# BW1097_HUB.net
KiCad netlist of a schematic drawn in Altium Designer
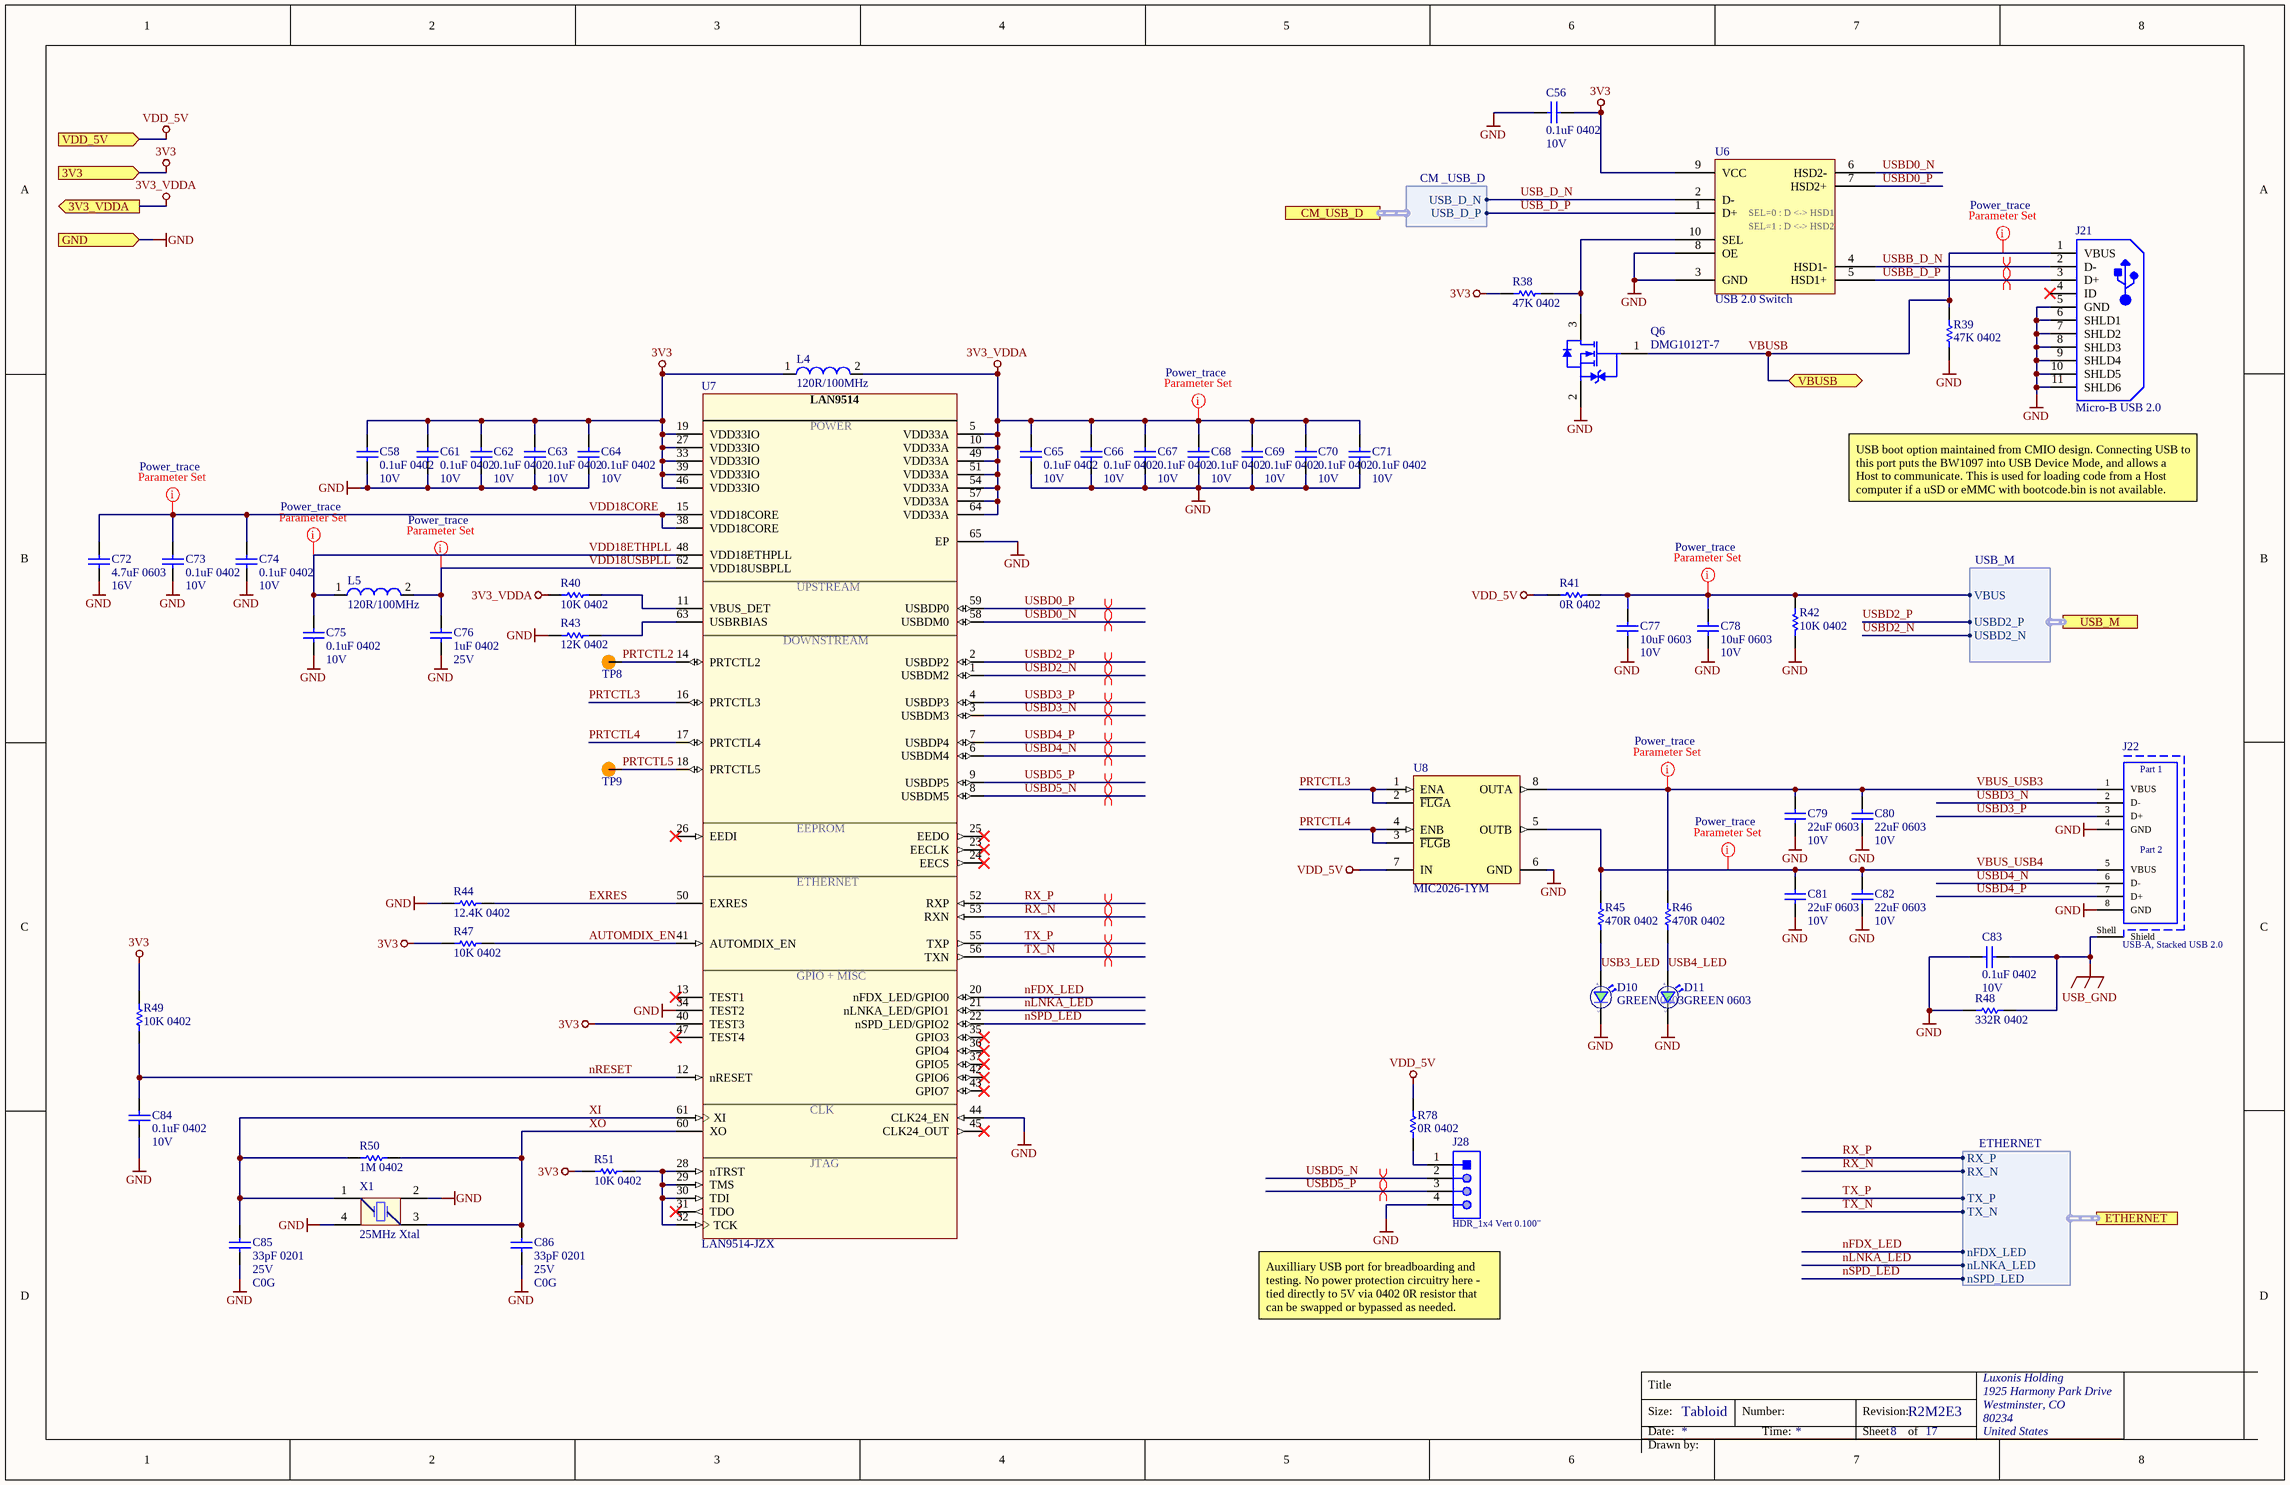
[diagram p0: BW1097_HUB.SchDoc]

(export (version "E")
  (design (tool "Eeschema 10.0.6"))
  (components
    (comp (ref "C56")
      (value "0.1uF 0402")
      (footprint "CAP_Altium_Vault_Generic:CAPC0402(1005)70_N")
      (description "CAP CER 0.1UF 10V X7R 0402 5%")
      (fields (field (name "TOLERANCE") "5%") (field (name "VOLTAGE RATING") "10V"))
      (libsource (lib "LuxonisMaster") (part "GRM155R71A104JA01D"))
    )
    (comp (ref "C58")
      (value "0.1uF 0402")
      (footprint "CAP_Altium_Vault_Generic:CAPC0402(1005)70_N")
      (description "CAP CER 0.1UF 10V X7R 0402 5%")
      (fields (field (name "TOLERANCE") "5%") (field (name "VOLTAGE RATING") "10V"))
      (libsource (lib "LuxonisMaster") (part "GRM155R71A104JA01D"))
    )
    (comp (ref "C61")
      (value "0.1uF 0402")
      (footprint "CAP_Altium_Vault_Generic:CAPC0402(1005)70_N")
      (description "CAP CER 0.1UF 10V X7R 0402 5%")
      (fields (field (name "TOLERANCE") "5%") (field (name "VOLTAGE RATING") "10V"))
      (libsource (lib "LuxonisMaster") (part "GRM155R71A104JA01D"))
    )
    (comp (ref "C62")
      (value "0.1uF 0402")
      (footprint "CAP_Altium_Vault_Generic:CAPC0402(1005)70_N")
      (description "CAP CER 0.1UF 10V X7R 0402 5%")
      (fields (field (name "TOLERANCE") "5%") (field (name "VOLTAGE RATING") "10V"))
      (libsource (lib "LuxonisMaster") (part "GRM155R71A104JA01D"))
    )
    (comp (ref "C63")
      (value "0.1uF 0402")
      (footprint "CAP_Altium_Vault_Generic:CAPC0402(1005)70_N")
      (description "CAP CER 0.1UF 10V X7R 0402 5%")
      (fields (field (name "TOLERANCE") "5%") (field (name "VOLTAGE RATING") "10V"))
      (libsource (lib "LuxonisMaster") (part "GRM155R71A104JA01D"))
    )
    (comp (ref "C64")
      (value "0.1uF 0402")
      (footprint "CAP_Altium_Vault_Generic:CAPC0402(1005)70_N")
      (description "CAP CER 0.1UF 10V X7R 0402 5%")
      (fields (field (name "TOLERANCE") "5%") (field (name "VOLTAGE RATING") "10V"))
      (libsource (lib "LuxonisMaster") (part "GRM155R71A104JA01D"))
    )
    (comp (ref "C65")
      (value "0.1uF 0402")
      (footprint "CAP_Altium_Vault_Generic:CAPC0402(1005)70_N")
      (description "CAP CER 0.1UF 10V X7R 0402 5%")
      (fields (field (name "TOLERANCE") "5%") (field (name "VOLTAGE RATING") "10V"))
      (libsource (lib "LuxonisMaster") (part "GRM155R71A104JA01D"))
    )
    (comp (ref "C66")
      (value "0.1uF 0402")
      (footprint "CAP_Altium_Vault_Generic:CAPC0402(1005)70_N")
      (description "CAP CER 0.1UF 10V X7R 0402 5%")
      (fields (field (name "TOLERANCE") "5%") (field (name "VOLTAGE RATING") "10V"))
      (libsource (lib "LuxonisMaster") (part "GRM155R71A104JA01D"))
    )
    (comp (ref "C67")
      (value "0.1uF 0402")
      (footprint "CAP_Altium_Vault_Generic:CAPC0402(1005)70_N")
      (description "CAP CER 0.1UF 10V X7R 0402 5%")
      (fields (field (name "TOLERANCE") "5%") (field (name "VOLTAGE RATING") "10V"))
      (libsource (lib "LuxonisMaster") (part "GRM155R71A104JA01D"))
    )
    (comp (ref "C68")
      (value "0.1uF 0402")
      (footprint "CAP_Altium_Vault_Generic:CAPC0402(1005)70_N")
      (description "CAP CER 0.1UF 10V X7R 0402 5%")
      (fields (field (name "TOLERANCE") "5%") (field (name "VOLTAGE RATING") "10V"))
      (libsource (lib "LuxonisMaster") (part "GRM155R71A104JA01D"))
    )
    (comp (ref "C69")
      (value "0.1uF 0402")
      (footprint "CAP_Altium_Vault_Generic:CAPC0402(1005)70_N")
      (description "CAP CER 0.1UF 10V X7R 0402 5%")
      (fields (field (name "TOLERANCE") "5%") (field (name "VOLTAGE RATING") "10V"))
      (libsource (lib "LuxonisMaster") (part "GRM155R71A104JA01D"))
    )
    (comp (ref "C70")
      (value "0.1uF 0402")
      (footprint "CAP_Altium_Vault_Generic:CAPC0402(1005)70_N")
      (description "CAP CER 0.1UF 10V X7R 0402 5%")
      (fields (field (name "TOLERANCE") "5%") (field (name "VOLTAGE RATING") "10V"))
      (libsource (lib "LuxonisMaster") (part "GRM155R71A104JA01D"))
    )
    (comp (ref "C71")
      (value "0.1uF 0402")
      (footprint "CAP_Altium_Vault_Generic:CAPC0402(1005)70_N")
      (description "CAP CER 0.1UF 10V X7R 0402 5%")
      (fields (field (name "TOLERANCE") "5%") (field (name "VOLTAGE RATING") "10V"))
      (libsource (lib "LuxonisMaster") (part "GRM155R71A104JA01D"))
    )
    (comp (ref "C72")
      (value "4.7uF 0603")
      (footprint "CAP_Altium_Vault_Generic:CAPC0603(1608)100_N")
      (description "CAP CER 4.7UF 16V X5R 0603 10%")
      (fields (field (name "TOLERANCE") "10%") (field (name "VOLTAGE RATING") "16V"))
      (libsource (lib "LuxonisMaster") (part "GRM188R61C475KAAJD"))
    )
    (comp (ref "C73")
      (value "0.1uF 0402")
      (footprint "CAP_Altium_Vault_Generic:CAPC0402(1005)70_N")
      (description "CAP CER 0.1UF 10V X7R 0402 5%")
      (fields (field (name "TOLERANCE") "5%") (field (name "VOLTAGE RATING") "10V"))
      (libsource (lib "LuxonisMaster") (part "GRM155R71A104JA01D"))
    )
    (comp (ref "C74")
      (value "0.1uF 0402")
      (footprint "CAP_Altium_Vault_Generic:CAPC0402(1005)70_N")
      (description "CAP CER 0.1UF 10V X7R 0402 5%")
      (fields (field (name "TOLERANCE") "5%") (field (name "VOLTAGE RATING") "10V"))
      (libsource (lib "LuxonisMaster") (part "GRM155R71A104JA01D"))
    )
    (comp (ref "C75")
      (value "0.1uF 0402")
      (footprint "CAP_Altium_Vault_Generic:CAPC0402(1005)70_N")
      (description "CAP CER 0.1UF 10V X7R 0402 5%")
      (fields (field (name "TOLERANCE") "5%") (field (name "VOLTAGE RATING") "10V"))
      (libsource (lib "LuxonisMaster") (part "GRM155R71A104JA01D"))
    )
    (comp (ref "C76")
      (value "1uF 0402")
      (footprint "CAP_Altium_Vault_Generic:CAPC0402(1005)70_N")
      (description "CAP CER 1UF 25V X5R 0402 10%")
      (fields
        (field (name "TOLERANCE") "10%")
        (field (name "VOLTAGE") "25V")
        (field (name "VOLTAGE RATING") "25V")
      )
      (libsource (lib "LuxonisMaster") (part "GRM155R61E105KA12D"))
    )
    (comp (ref "C77")
      (value "10uF 0603")
      (footprint "CAP_Altium_Vault_Generic:CAPC0603(1608)100_N")
      (description "CAP CER 10UF 10V X5R 0603 20%")
      (fields (field (name "TOLERANCE") "20%") (field (name "VOLTAGE RATING") "10V"))
      (libsource (lib "LuxonisMaster") (part "GRM188R61A106ME69D"))
    )
    (comp (ref "C78")
      (value "10uF 0603")
      (footprint "CAP_Altium_Vault_Generic:CAPC0603(1608)100_N")
      (description "CAP CER 10UF 10V X5R 0603 20%")
      (fields (field (name "TOLERANCE") "20%") (field (name "VOLTAGE RATING") "10V"))
      (libsource (lib "LuxonisMaster") (part "GRM188R61A106ME69D"))
    )
    (comp (ref "C79")
      (value "22uF 0603")
      (footprint "CAP_Altium_Vault_Generic:CAPC0603(1608)100_N")
      (description "CAP CER 22UF 10V X5R 0603 20%")
      (fields (field (name "TOLERANCE") "20%") (field (name "VOLTAGE RATING") "10V"))
      (libsource (lib "LuxonisMaster") (part "GRM188R61A226ME15D"))
    )
    (comp (ref "C80")
      (value "22uF 0603")
      (footprint "CAP_Altium_Vault_Generic:CAPC0603(1608)100_N")
      (description "CAP CER 22UF 10V X5R 0603 20%")
      (fields (field (name "TOLERANCE") "20%") (field (name "VOLTAGE RATING") "10V"))
      (libsource (lib "LuxonisMaster") (part "GRM188R61A226ME15D"))
    )
    (comp (ref "C81")
      (value "22uF 0603")
      (footprint "CAP_Altium_Vault_Generic:CAPC0603(1608)100_N")
      (description "CAP CER 22UF 10V X5R 0603 20%")
      (fields (field (name "TOLERANCE") "20%") (field (name "VOLTAGE RATING") "10V"))
      (libsource (lib "LuxonisMaster") (part "GRM188R61A226ME15D"))
    )
    (comp (ref "C82")
      (value "22uF 0603")
      (footprint "CAP_Altium_Vault_Generic:CAPC0603(1608)100_N")
      (description "CAP CER 22UF 10V X5R 0603 20%")
      (fields (field (name "TOLERANCE") "20%") (field (name "VOLTAGE RATING") "10V"))
      (libsource (lib "LuxonisMaster") (part "GRM188R61A226ME15D"))
    )
    (comp (ref "C83")
      (value "0.1uF 0402")
      (footprint "CAP_Altium_Vault_Generic:CAPC0402(1005)70_N")
      (description "CAP CER 0.1UF 10V X7R 0402 5%")
      (fields (field (name "TOLERANCE") "5%") (field (name "VOLTAGE RATING") "10V"))
      (libsource (lib "LuxonisMaster") (part "GRM155R71A104JA01D"))
    )
    (comp (ref "C84")
      (value "0.1uF 0402")
      (footprint "CAP_Altium_Vault_Generic:CAPC0402(1005)70_N")
      (description "CAP CER 0.1UF 10V X7R 0402 5%")
      (fields (field (name "TOLERANCE") "5%") (field (name "VOLTAGE RATING") "10V"))
      (libsource (lib "LuxonisMaster") (part "GRM155R71A104JA01D"))
    )
    (comp (ref "C85")
      (value "33pF 0201")
      (footprint "CAP_Altium_Vault_Generic:CAPC0201(0603)33_L")
      (description "CAP CER 33PF 25V C0G/NP0 0201")
      (fields
        (field (name "TOLERANCE") "5%")
        (field (name "VOLTAGE RATING") "25V")
        (field (name "DIELECTRIC") "C0G")
      )
      (libsource (lib "LuxonisMaster") (part "GRM0335C1E330JA01D"))
    )
    (comp (ref "C86")
      (value "33pF 0201")
      (footprint "CAP_Altium_Vault_Generic:CAPC0201(0603)33_L")
      (description "CAP CER 33PF 25V C0G/NP0 0201")
      (fields
        (field (name "TOLERANCE") "5%")
        (field (name "VOLTAGE RATING") "25V")
        (field (name "DIELECTRIC") "C0G")
      )
      (libsource (lib "LuxonisMaster") (part "GRM0335C1E330JA01D"))
    )
    (comp (ref "D10")
      (value "GREEN 0603")
      (footprint "LuxonisMaster:SML_D1xx8W")
      (description "LED GREEN DIFFUSED 0603 SMD Green 572nm LED Indication - Discrete 2.2V 0603 (1608 Metric)")
      (fields (field (name "MANUFACTURER") "Rohm") (field (name "MANUFACTURER PART NUMBER") "SML-D12M8WT86"))
      (libsource (lib "LuxonisMaster") (part "SML-D12M8WT86"))
    )
    (comp (ref "D11")
      (value "GREEN 0603")
      (footprint "LuxonisMaster:SML_D1xx8W")
      (description "LED GREEN DIFFUSED 0603 SMD Green 572nm LED Indication - Discrete 2.2V 0603 (1608 Metric)")
      (fields (field (name "MANUFACTURER") "Rohm") (field (name "MANUFACTURER PART NUMBER") "SML-D12M8WT86"))
      (libsource (lib "LuxonisMaster") (part "SML-D12M8WT86"))
    )
    (comp (ref "J21")
      (value "Micro-B USB 2.0")
      (footprint "LuxonisMaster:10118194-0001LF")
      (libsource (lib "LuxonisMaster") (part "10118194-0001LF"))
    )
    (comp (ref "J22")
      (value "USB-A, Stacked USB 2.0")
      (footprint "LuxonisMaster:61400826021")
      (libsource (lib "LuxonisMaster") (part "61400826021"))
    )
    (comp (ref "J28")
      (value "HDR_1x4 Vert 0.100\"")
      (footprint "LuxonisMaster:61300411121")
      (description "CONN HEADER VERT 4POS 2.54MM  Connector Header Through Hole 4 position 0.100\" (2.54mm)")
      (libsource (lib "LuxonisMaster") (part "61300411121"))
    )
    (comp (ref "L4")
      (value "120R/100MHz")
      (footprint "LuxonisMaster:BLM18PG121SN1D_N")
      (description "FERRITE BEAD 120 OHM 0603 1LN")
      (fields (field (name "TOLERANCE") "25%"))
      (libsource (lib "LuxonisMaster") (part "BLM18PG121SN1D"))
    )
    (comp (ref "L5")
      (value "120R/100MHz")
      (footprint "LuxonisMaster:BLM18PG121SN1D_N")
      (description "FERRITE BEAD 120 OHM 0603 1LN")
      (fields (field (name "TOLERANCE") "25%"))
      (libsource (lib "LuxonisMaster") (part "BLM18PG121SN1D"))
    )
    (comp (ref "Q6")
      (value "DMG1012T-7")
      (footprint "LuxonisMaster:DMG1012T-7")
      (description "MOSFET N-CH 20V 630MA SOT-523")
      (libsource (lib "LuxonisMaster") (part "DMG1012T-7"))
    )
    (comp (ref "R38")
      (value "47K 0402")
      (footprint "RES_Altium_Vault_Generic:RESC0402(1005)_N")
      (description "RES SMD 47K OHM 1% 1/16W 0402")
      (fields (field (name "TOLERANCE") "1%"))
      (libsource (lib "LuxonisMaster") (part "RC0402FR-0747KL"))
    )
    (comp (ref "R39")
      (value "47K 0402")
      (footprint "RES_Altium_Vault_Generic:RESC0402(1005)_N")
      (description "RES SMD 47K OHM 1% 1/16W 0402")
      (fields (field (name "TOLERANCE") "1%"))
      (libsource (lib "LuxonisMaster") (part "RC0402FR-0747KL"))
    )
    (comp (ref "R40")
      (value "10K 0402")
      (footprint "RES_Altium_Vault_Generic:RESC0402(1005)_N")
      (fields (field (name "TOLERANCE") "1%"))
      (libsource (lib "LuxonisMaster") (part "RC0402FR-1310KL"))
    )
    (comp (ref "R41")
      (value "0R 0402")
      (footprint "RES_Altium_Vault_Generic:RESC0402(1005)_N")
      (description "RES SMD 0 OHM JUMPER 1/16W 0402")
      (fields (field (name "TOLERANCE") "5%"))
      (libsource (lib "LuxonisMaster") (part "CRCW04020000Z0ED"))
    )
    (comp (ref "R42")
      (value "10K 0402")
      (footprint "RES_Altium_Vault_Generic:RESC0402(1005)_N")
      (fields (field (name "TOLERANCE") "1%"))
      (libsource (lib "LuxonisMaster") (part "RC0402FR-1310KL"))
    )
    (comp (ref "R43")
      (value "12K 0402")
      (footprint "RES_Altium_Vault_Generic:RESC0402(1005)_N")
      (fields (field (name "TOLERANCE") "1%"))
      (libsource (lib "LuxonisMaster") (part "RC0402FR-0712KL"))
    )
    (comp (ref "R44")
      (value "12.4K 0402")
      (footprint "RES_Altium_Vault_Generic:RESC0402(1005)_N")
      (description "RES SMD 12.4K OHM 1% 1/16W 0402")
      (fields (field (name "TOLERANCE") "1%"))
      (libsource (lib "LuxonisMaster") (part "RC0402FR-0712K4L"))
    )
    (comp (ref "R45")
      (value "470R 0402")
      (footprint "RES_Altium_Vault_Generic:RESC0402(1005)_N")
      (description "RES SMD 470 OHM 1% 1/16W 0402")
      (fields (field (name "TOLERANCE") "1%"))
      (libsource (lib "LuxonisMaster") (part "CRCW0402470RFKED"))
    )
    (comp (ref "R46")
      (value "470R 0402")
      (footprint "RES_Altium_Vault_Generic:RESC0402(1005)_N")
      (description "RES SMD 470 OHM 1% 1/16W 0402")
      (fields (field (name "TOLERANCE") "1%"))
      (libsource (lib "LuxonisMaster") (part "CRCW0402470RFKED"))
    )
    (comp (ref "R47")
      (value "10K 0402")
      (footprint "RES_Altium_Vault_Generic:RESC0402(1005)_N")
      (fields (field (name "TOLERANCE") "1%"))
      (libsource (lib "LuxonisMaster") (part "RC0402FR-1310KL"))
    )
    (comp (ref "R48")
      (value "332R 0402")
      (footprint "RES_Altium_Vault_Generic:RESC0402(1005)_N")
      (description "RES SMD 332 OHM 1% 1/16W 0402")
      (fields (field (name "TOLERANCE") "1%"))
      (libsource (lib "LuxonisMaster") (part "RC0402FR-07332RL"))
    )
    (comp (ref "R49")
      (value "10K 0402")
      (footprint "RES_Altium_Vault_Generic:RESC0402(1005)_N")
      (fields (field (name "TOLERANCE") "1%"))
      (libsource (lib "LuxonisMaster") (part "RC0402FR-1310KL"))
    )
    (comp (ref "R50")
      (value "1M 0402")
      (footprint "RES_Altium_Vault_Generic:RESC0402(1005)_N")
      (description "RES SMD 1M OHM 1% 1/16W 0402")
      (fields (field (name "TOLERANCE") "1%"))
      (libsource (lib "LuxonisMaster") (part "RC0402FR-071ML"))
    )
    (comp (ref "R51")
      (value "10K 0402")
      (footprint "RES_Altium_Vault_Generic:RESC0402(1005)_N")
      (fields (field (name "TOLERANCE") "1%"))
      (libsource (lib "LuxonisMaster") (part "RC0402FR-1310KL"))
    )
    (comp (ref "R78")
      (value "0R 0402")
      (footprint "RES_Altium_Vault_Generic:RESC0402(1005)_N")
      (description "RES SMD 0 OHM JUMPER 1/16W 0402")
      (fields (field (name "TOLERANCE") "5%"))
      (libsource (lib "LuxonisMaster") (part "CRCW04020000Z0ED"))
    )
    (comp (ref "TP8")
      (value "TP100_200_NS")
      (footprint "LuxonisMaster:TP100_200_NS")
      (libsource (lib "LuxonisMaster") (part "TEST_POINT"))
    )
    (comp (ref "TP9")
      (value "TP100_200_NS")
      (footprint "LuxonisMaster:TP100_200_NS")
      (libsource (lib "LuxonisMaster") (part "TEST_POINT"))
    )
    (comp (ref "U6")
      (value "USB 2.0 Switch")
      (footprint "LuxonisMaster:FSUSB42UMX")
      (description "IC USB SWITCH DPDT 10UMLP")
      (libsource (lib "LuxonisMaster") (part "FSUSB42UMX"))
    )
    (comp (ref "U7")
      (value "LAN9514-JZX")
      (footprint "LuxonisMaster:LAN951x-JZX")
      (libsource (lib "LuxonisMaster") (part "LAN9514-JZX"))
    )
    (comp (ref "U8")
      (value "MIC2026-1YM")
      (footprint "LuxonisMaster:MIC2026-1YM")
      (description "IC PW DIST SW DUAL 8SOIC Power Switch/Driver 1:2 N-Channel 500mA 8-SOIC")
      (fields (field (name "MANUFACTURER") "Micrel"))
      (libsource (lib "LuxonisMaster") (part "MIC2026-1YM"))
    )
    (comp (ref "X1")
      (value "25MHz Xtal")
      (footprint "LuxonisMaster:8Z-25.000MAAJ-T")
      (description "CRYSTAL 25.0000MHZ 18PF SMD")
      (fields (field (name "TOLERANCE") "30ppm"))
      (libsource (lib "LuxonisMaster") (part "8Z-25.000MAAJ-T"))
    )
  )
  (nets
    (net (code "5") (name "/AUTOMDIX_EN") (class "Default")
      (node (ref "R47") (pin "2") (pinfunction "2_2") (pintype "passive"))
      (node (ref "U7") (pin "41") (pinfunction "AUTOMDIX_EN_41") (pintype "input"))
    )
    (net (code "6") (name "/EXRES") (class "Default")
      (node (ref "R44") (pin "2") (pinfunction "2_2") (pintype "passive"))
      (node (ref "U7") (pin "50") (pinfunction "EXRES_50") (pintype "passive"))
    )
    (net (code "7") (name "/PRTCTL2") (class "Default")
      (node (ref "TP8") (pin "1") (pintype "passive"))
      (node (ref "U7") (pin "14") (pinfunction "PRTCTL2_14") (pintype "bidirectional"))
    )
    (net (code "8") (name "/PRTCTL3") (class "Default")
      (node (ref "U7") (pin "16") (pinfunction "PRTCTL3_16") (pintype "bidirectional"))
      (node (ref "U8") (pin "1") (pinfunction "ENA_1") (pintype "input"))
      (node (ref "U8") (pin "2") (pinfunction "~{FLG}A_2") (pintype "open_collector"))
    )
    (net (code "9") (name "/PRTCTL4") (class "Default")
      (node (ref "U7") (pin "17") (pinfunction "PRTCTL4_17") (pintype "bidirectional"))
      (node (ref "U8") (pin "3") (pinfunction "~{FLG}B_3") (pintype "open_collector"))
      (node (ref "U8") (pin "4") (pinfunction "ENB_4") (pintype "input"))
    )
    (net (code "10") (name "/PRTCTL5") (class "Default")
      (node (ref "TP9") (pin "1") (pintype "passive"))
      (node (ref "U7") (pin "18") (pinfunction "PRTCTL5_18") (pintype "bidirectional"))
    )
    (net (code "11") (name "/RX_N") (class "Default")
      (node (ref "U7") (pin "53") (pinfunction "RXN_53") (pintype "input"))
    )
    (net (code "12") (name "/RX_P") (class "Default")
      (node (ref "U7") (pin "52") (pinfunction "RXP_52") (pintype "input"))
    )
    (net (code "13") (name "/TX_N") (class "Default")
      (node (ref "U7") (pin "56") (pinfunction "TXN_56") (pintype "output"))
    )
    (net (code "14") (name "/TX_P") (class "Default")
      (node (ref "U7") (pin "55") (pinfunction "TXP_55") (pintype "output"))
    )
    (net (code "15") (name "/USB3_LED") (class "Default")
      (node (ref "D10") (pin "2") (pinfunction "A_2") (pintype "passive"))
      (node (ref "R45") (pin "1") (pinfunction "1_1") (pintype "passive"))
    )
    (net (code "16") (name "/USB4_LED") (class "Default")
      (node (ref "D11") (pin "2") (pinfunction "A_2") (pintype "passive"))
      (node (ref "R46") (pin "1") (pinfunction "1_1") (pintype "passive"))
    )
    (net (code "17") (name "/USBB_D_N") (class "Default")
      (node (ref "J21") (pin "2") (pinfunction "D-_2") (pintype "passive"))
      (node (ref "U6") (pin "4") (pinfunction "HSD1-_4") (pintype "passive"))
    )
    (net (code "18") (name "/USBB_D_P") (class "Default")
      (node (ref "J21") (pin "3") (pinfunction "D+_3") (pintype "passive"))
      (node (ref "U6") (pin "5") (pinfunction "HSD1+_5") (pintype "passive"))
    )
    (net (code "19") (name "/USBD0_N") (class "Default")
      (node (ref "U6") (pin "6") (pinfunction "HSD2-_6") (pintype "passive"))
      (node (ref "U7") (pin "58") (pinfunction "USBDM0_58") (pintype "bidirectional"))
    )
    (net (code "20") (name "/USBD0_P") (class "Default")
      (node (ref "U6") (pin "7") (pinfunction "HSD2+_7") (pintype "passive"))
      (node (ref "U7") (pin "59") (pinfunction "USBDP0_59") (pintype "bidirectional"))
    )
    (net (code "21") (name "/USBD2_N") (class "Default")
      (node (ref "U7") (pin "1") (pinfunction "USBDM2_1") (pintype "bidirectional"))
    )
    (net (code "22") (name "/USBD2_P") (class "Default")
      (node (ref "U7") (pin "2") (pinfunction "USBDP2_2") (pintype "bidirectional"))
    )
    (net (code "23") (name "/USBD3_N") (class "Default")
      (node (ref "J22") (pin "2") (pinfunction "D-_2") (pintype "passive"))
      (node (ref "U7") (pin "3") (pinfunction "USBDM3_3") (pintype "bidirectional"))
    )
    (net (code "24") (name "/USBD3_P") (class "Default")
      (node (ref "J22") (pin "3") (pinfunction "D+_3") (pintype "passive"))
      (node (ref "U7") (pin "4") (pinfunction "USBDP3_4") (pintype "bidirectional"))
    )
    (net (code "25") (name "/USBD4_N") (class "Default")
      (node (ref "J22") (pin "6") (pinfunction "D-_6") (pintype "passive"))
      (node (ref "U7") (pin "6") (pinfunction "USBDM4_6") (pintype "bidirectional"))
    )
    (net (code "26") (name "/USBD4_P") (class "Default")
      (node (ref "J22") (pin "7") (pinfunction "D+_7") (pintype "passive"))
      (node (ref "U7") (pin "7") (pinfunction "USBDP4_7") (pintype "bidirectional"))
    )
    (net (code "27") (name "/USBD5_N") (class "Default")
      (node (ref "J28") (pin "2") (pinfunction "2_2") (pintype "passive"))
      (node (ref "U7") (pin "8") (pinfunction "USBDM5_8") (pintype "bidirectional"))
    )
    (net (code "28") (name "/USBD5_P") (class "Default")
      (node (ref "J28") (pin "3") (pinfunction "3_3") (pintype "passive"))
      (node (ref "U7") (pin "9") (pinfunction "USBDP5_9") (pintype "bidirectional"))
    )
    (net (code "29") (name "/USB_D_N") (class "Default")
      (node (ref "U6") (pin "2") (pinfunction "D-_2") (pintype "passive"))
    )
    (net (code "30") (name "/USB_D_P") (class "Default")
      (node (ref "U6") (pin "1") (pinfunction "D+_1") (pintype "passive"))
    )
    (net (code "31") (name "/VBUSB") (class "Default")
      (node (ref "J21") (pin "1") (pinfunction "VBUS_1") (pintype "passive"))
      (node (ref "Q6") (pin "1") (pinfunction "1_1") (pintype "passive"))
      (node (ref "R39") (pin "2") (pinfunction "2_2") (pintype "passive"))
    )
    (net (code "32") (name "/VBUS_USB3") (class "Default")
      (node (ref "C79") (pin "1") (pinfunction "1_1") (pintype "passive"))
      (node (ref "C80") (pin "1") (pinfunction "1_1") (pintype "passive"))
      (node (ref "J22") (pin "1") (pinfunction "VBUS_1") (pintype "passive"))
      (node (ref "R46") (pin "2") (pinfunction "2_2") (pintype "passive"))
      (node (ref "U8") (pin "8") (pinfunction "OUTA_8") (pintype "output"))
    )
    (net (code "33") (name "/VBUS_USB4") (class "Default")
      (node (ref "C81") (pin "1") (pinfunction "1_1") (pintype "passive"))
      (node (ref "C82") (pin "1") (pinfunction "1_1") (pintype "passive"))
      (node (ref "J22") (pin "5") (pinfunction "VBUS_5") (pintype "passive"))
      (node (ref "R45") (pin "2") (pinfunction "2_2") (pintype "passive"))
      (node (ref "U8") (pin "5") (pinfunction "OUTB_5") (pintype "output"))
    )
    (net (code "34") (name "/VDD18CORE") (class "Default")
      (node (ref "C72") (pin "2") (pinfunction "2_2") (pintype "passive"))
      (node (ref "C73") (pin "2") (pinfunction "2_2") (pintype "passive"))
      (node (ref "C74") (pin "2") (pinfunction "2_2") (pintype "passive"))
      (node (ref "U7") (pin "15") (pinfunction "VDD18CORE_15") (pintype "power_in"))
      (node (ref "U7") (pin "38") (pinfunction "VDD18CORE_38") (pintype "power_in"))
    )
    (net (code "35") (name "/VDD18ETHPLL") (class "Default")
      (node (ref "C75") (pin "2") (pinfunction "2_2") (pintype "passive"))
      (node (ref "L5") (pin "1") (pinfunction "1_1") (pintype "passive"))
      (node (ref "U7") (pin "48") (pinfunction "VDD18ETHPLL_48") (pintype "power_in"))
    )
    (net (code "36") (name "/VDD18USBPLL") (class "Default")
      (node (ref "C76") (pin "2") (pinfunction "2_2") (pintype "passive"))
      (node (ref "L5") (pin "2") (pinfunction "2_2") (pintype "passive"))
      (node (ref "U7") (pin "62") (pinfunction "VDD18USBPLL_62") (pintype "power_in"))
    )
    (net (code "37") (name "/XI") (class "Default")
      (node (ref "C85") (pin "2") (pinfunction "2_2") (pintype "passive"))
      (node (ref "R50") (pin "1") (pinfunction "1_1") (pintype "passive"))
      (node (ref "U7") (pin "61") (pinfunction "XI_61") (pintype "input"))
      (node (ref "X1") (pin "1") (pinfunction "OSC1_1") (pintype "passive"))
    )
    (net (code "38") (name "/XO") (class "Default")
      (node (ref "C86") (pin "2") (pinfunction "2_2") (pintype "passive"))
      (node (ref "R50") (pin "2") (pinfunction "2_2") (pintype "passive"))
      (node (ref "U7") (pin "60") (pinfunction "XO_60") (pintype "passive"))
      (node (ref "X1") (pin "3") (pinfunction "OSC3_3") (pintype "passive"))
    )
    (net (code "39") (name "/nFDX_LED") (class "Default")
      (node (ref "U7") (pin "20") (pinfunction "nFDX_LED/GPIO0_20") (pintype "bidirectional"))
    )
    (net (code "40") (name "/nLNKA_LED") (class "Default")
      (node (ref "U7") (pin "21") (pinfunction "nLNKA_LED/GPIO1_21") (pintype "bidirectional"))
    )
    (net (code "41") (name "/nRESET") (class "Default")
      (node (ref "C84") (pin "2") (pinfunction "2_2") (pintype "passive"))
      (node (ref "R49") (pin "2") (pinfunction "2_2") (pintype "passive"))
      (node (ref "U7") (pin "12") (pinfunction "nRESET_12") (pintype "input"))
    )
    (net (code "42") (name "/nSPD_LED") (class "Default")
      (node (ref "U7") (pin "22") (pinfunction "nSPD_LED/GPIO2_22") (pintype "bidirectional"))
    )
    (net (code "46") (name "3V3") (class "Default")
      (node (ref "C56") (pin "1") (pinfunction "1_1") (pintype "passive"))
      (node (ref "C58") (pin "2") (pinfunction "2_2") (pintype "passive"))
      (node (ref "C61") (pin "2") (pinfunction "2_2") (pintype "passive"))
      (node (ref "C62") (pin "2") (pinfunction "2_2") (pintype "passive"))
      (node (ref "C63") (pin "2") (pinfunction "2_2") (pintype "passive"))
      (node (ref "C64") (pin "2") (pinfunction "2_2") (pintype "passive"))
      (node (ref "L4") (pin "1") (pinfunction "1_1") (pintype "passive"))
      (node (ref "R38") (pin "1") (pinfunction "1_1") (pintype "passive"))
      (node (ref "R47") (pin "1") (pinfunction "1_1") (pintype "passive"))
      (node (ref "R49") (pin "1") (pinfunction "1_1") (pintype "passive"))
      (node (ref "R51") (pin "1") (pinfunction "1_1") (pintype "passive"))
      (node (ref "U6") (pin "9") (pinfunction "VCC_9") (pintype "passive"))
      (node (ref "U7") (pin "19") (pinfunction "VDD33IO_19") (pintype "power_in"))
      (node (ref "U7") (pin "27") (pinfunction "VDD33IO_27") (pintype "power_in"))
      (node (ref "U7") (pin "33") (pinfunction "VDD33IO_33") (pintype "power_in"))
      (node (ref "U7") (pin "39") (pinfunction "VDD33IO_39") (pintype "power_in"))
      (node (ref "U7") (pin "40") (pinfunction "TEST3_40") (pintype "passive"))
      (node (ref "U7") (pin "46") (pinfunction "VDD33IO_46") (pintype "power_in"))
    )
    (net (code "47") (name "3V3_VDDA") (class "Default")
      (node (ref "C65") (pin "2") (pinfunction "2_2") (pintype "passive"))
      (node (ref "C66") (pin "2") (pinfunction "2_2") (pintype "passive"))
      (node (ref "C67") (pin "2") (pinfunction "2_2") (pintype "passive"))
      (node (ref "C68") (pin "2") (pinfunction "2_2") (pintype "passive"))
      (node (ref "C69") (pin "2") (pinfunction "2_2") (pintype "passive"))
      (node (ref "C70") (pin "2") (pinfunction "2_2") (pintype "passive"))
      (node (ref "C71") (pin "2") (pinfunction "2_2") (pintype "passive"))
      (node (ref "L4") (pin "2") (pinfunction "2_2") (pintype "passive"))
      (node (ref "R40") (pin "1") (pinfunction "1_1") (pintype "passive"))
      (node (ref "U7") (pin "10") (pinfunction "VDD33A_10") (pintype "power_in"))
      (node (ref "U7") (pin "49") (pinfunction "VDD33A_49") (pintype "power_in"))
      (node (ref "U7") (pin "5") (pinfunction "VDD33A_5") (pintype "power_in"))
      (node (ref "U7") (pin "51") (pinfunction "VDD33A_51") (pintype "power_in"))
      (node (ref "U7") (pin "54") (pinfunction "VDD33A_54") (pintype "power_in"))
      (node (ref "U7") (pin "57") (pinfunction "VDD33A_57") (pintype "power_in"))
      (node (ref "U7") (pin "64") (pinfunction "VDD33A_64") (pintype "power_in"))
    )
    (net (code "48") (name "GND") (class "Default")
      (node (ref "C56") (pin "2") (pinfunction "2_2") (pintype "passive"))
      (node (ref "C58") (pin "1") (pinfunction "1_1") (pintype "passive"))
      (node (ref "C61") (pin "1") (pinfunction "1_1") (pintype "passive"))
      (node (ref "C62") (pin "1") (pinfunction "1_1") (pintype "passive"))
      (node (ref "C63") (pin "1") (pinfunction "1_1") (pintype "passive"))
      (node (ref "C64") (pin "1") (pinfunction "1_1") (pintype "passive"))
      (node (ref "C65") (pin "1") (pinfunction "1_1") (pintype "passive"))
      (node (ref "C66") (pin "1") (pinfunction "1_1") (pintype "passive"))
      (node (ref "C67") (pin "1") (pinfunction "1_1") (pintype "passive"))
      (node (ref "C68") (pin "1") (pinfunction "1_1") (pintype "passive"))
      (node (ref "C69") (pin "1") (pinfunction "1_1") (pintype "passive"))
      (node (ref "C70") (pin "1") (pinfunction "1_1") (pintype "passive"))
      (node (ref "C71") (pin "1") (pinfunction "1_1") (pintype "passive"))
      (node (ref "C72") (pin "1") (pinfunction "1_1") (pintype "passive"))
      (node (ref "C73") (pin "1") (pinfunction "1_1") (pintype "passive"))
      (node (ref "C74") (pin "1") (pinfunction "1_1") (pintype "passive"))
      (node (ref "C75") (pin "1") (pinfunction "1_1") (pintype "passive"))
      (node (ref "C76") (pin "1") (pinfunction "1_1") (pintype "passive"))
      (node (ref "C77") (pin "1") (pinfunction "1_1") (pintype "passive"))
      (node (ref "C78") (pin "1") (pinfunction "1_1") (pintype "passive"))
      (node (ref "C79") (pin "2") (pinfunction "2_2") (pintype "passive"))
      (node (ref "C80") (pin "2") (pinfunction "2_2") (pintype "passive"))
      (node (ref "C81") (pin "2") (pinfunction "2_2") (pintype "passive"))
      (node (ref "C82") (pin "2") (pinfunction "2_2") (pintype "passive"))
      (node (ref "C83") (pin "1") (pinfunction "1_1") (pintype "passive"))
      (node (ref "C84") (pin "1") (pinfunction "1_1") (pintype "passive"))
      (node (ref "C85") (pin "1") (pinfunction "1_1") (pintype "passive"))
      (node (ref "C86") (pin "1") (pinfunction "1_1") (pintype "passive"))
      (node (ref "D10") (pin "1") (pinfunction "C_1") (pintype "passive"))
      (node (ref "D11") (pin "1") (pinfunction "C_1") (pintype "passive"))
      (node (ref "J21") (pin "10") (pinfunction "SHLD5_10") (pintype "passive"))
      (node (ref "J21") (pin "11") (pinfunction "SHLD6_11") (pintype "passive"))
      (node (ref "J21") (pin "5") (pinfunction "GND_5") (pintype "passive"))
      (node (ref "J21") (pin "6") (pinfunction "SHLD1_6") (pintype "passive"))
      (node (ref "J21") (pin "7") (pinfunction "SHLD2_7") (pintype "passive"))
      (node (ref "J21") (pin "8") (pinfunction "SHLD3_8") (pintype "passive"))
      (node (ref "J21") (pin "9") (pinfunction "SHLD4_9") (pintype "passive"))
      (node (ref "J22") (pin "4") (pinfunction "GND_4") (pintype "passive"))
      (node (ref "J22") (pin "8") (pinfunction "GND_8") (pintype "passive"))
      (node (ref "J28") (pin "4") (pinfunction "4_4") (pintype "passive"))
      (node (ref "Q6") (pin "2") (pinfunction "2_2") (pintype "passive"))
      (node (ref "R39") (pin "1") (pinfunction "1_1") (pintype "passive"))
      (node (ref "R42") (pin "1") (pinfunction "1_1") (pintype "passive"))
      (node (ref "R43") (pin "1") (pinfunction "1_1") (pintype "passive"))
      (node (ref "R44") (pin "1") (pinfunction "1_1") (pintype "passive"))
      (node (ref "R48") (pin "1") (pinfunction "1_1") (pintype "passive"))
      (node (ref "U6") (pin "3") (pinfunction "GND_3") (pintype "passive"))
      (node (ref "U6") (pin "8") (pinfunction "OE_8") (pintype "passive"))
      (node (ref "U7") (pin "34") (pinfunction "TEST2_34") (pintype "passive"))
      (node (ref "U7") (pin "44") (pinfunction "CLK24_EN_44") (pintype "input"))
      (node (ref "U7") (pin "65") (pinfunction "EP_65") (pintype "power_in"))
      (node (ref "U8") (pin "6") (pinfunction "GND_6") (pintype "power_in"))
      (node (ref "X1") (pin "2") (pinfunction "2_2") (pintype "passive"))
      (node (ref "X1") (pin "4") (pinfunction "4_4") (pintype "passive"))
    )
    (net (code "49") (name "Net-(C77-Pad2)") (class "Default")
      (node (ref "C77") (pin "2") (pinfunction "2_2") (pintype "passive"))
      (node (ref "C78") (pin "2") (pinfunction "2_2") (pintype "passive"))
      (node (ref "R41") (pin "1") (pinfunction "1_1") (pintype "passive"))
      (node (ref "R42") (pin "2") (pinfunction "2_2") (pintype "passive"))
    )
    (net (code "50") (name "Net-(J28-Pad1)") (class "Default")
      (node (ref "J28") (pin "1") (pinfunction "1_1") (pintype "passive"))
      (node (ref "R78") (pin "1") (pinfunction "1_1") (pintype "passive"))
    )
    (net (code "51") (name "Net-(U6-SEL)") (class "Default")
      (node (ref "Q6") (pin "3") (pinfunction "3_3") (pintype "passive"))
      (node (ref "R38") (pin "2") (pinfunction "2_2") (pintype "passive"))
      (node (ref "U6") (pin "10") (pinfunction "SEL_10") (pintype "passive"))
    )
    (net (code "52") (name "Net-(U7-TCK)") (class "Default")
      (node (ref "R51") (pin "2") (pinfunction "2_2") (pintype "passive"))
      (node (ref "U7") (pin "28") (pinfunction "nTRST_28") (pintype "input"))
      (node (ref "U7") (pin "29") (pinfunction "TMS_29") (pintype "input"))
      (node (ref "U7") (pin "30") (pinfunction "TDI_30") (pintype "input"))
      (node (ref "U7") (pin "32") (pinfunction "TCK_32") (pintype "input"))
    )
    (net (code "53") (name "Net-(U7-USBRBIAS)") (class "Default")
      (node (ref "R43") (pin "2") (pinfunction "2_2") (pintype "passive"))
      (node (ref "U7") (pin "63") (pinfunction "USBRBIAS_63") (pintype "passive"))
    )
    (net (code "54") (name "Net-(U7-VBUS_DET)") (class "Default")
      (node (ref "R40") (pin "2") (pinfunction "2_2") (pintype "passive"))
      (node (ref "U7") (pin "11") (pinfunction "VBUS_DET_11") (pintype "power_in"))
    )
    (net (code "55") (name "USB_GND") (class "Default")
      (node (ref "C83") (pin "2") (pinfunction "2_2") (pintype "passive"))
      (node (ref "J22") (pin "Shell") (pinfunction "Shield_Shell") (pintype "passive"))
      (node (ref "R48") (pin "2") (pinfunction "2_2") (pintype "passive"))
    )
    (net (code "56") (name "VDD_5V") (class "Default")
      (node (ref "R41") (pin "2") (pinfunction "2_2") (pintype "passive"))
      (node (ref "R78") (pin "2") (pinfunction "2_2") (pintype "passive"))
      (node (ref "U8") (pin "7") (pinfunction "IN_7") (pintype "power_in"))
    )
    (net (code "57") (name "unconnected-(J21-ID-Pad4)") (class "Default")
      (node (ref "J21") (pin "4") (pinfunction "ID_4") (pintype "passive+no_connect"))
    )
    (net (code "58") (name "unconnected-(U7-CLK24_OUT-Pad45)") (class "Default")
      (node (ref "U7") (pin "45") (pinfunction "CLK24_OUT_45") (pintype "output+no_connect"))
    )
    (net (code "59") (name "unconnected-(U7-EECLK-Pad23)") (class "Default")
      (node (ref "U7") (pin "23") (pinfunction "EECLK_23") (pintype "output+no_connect"))
    )
    (net (code "60") (name "unconnected-(U7-EECS-Pad24)") (class "Default")
      (node (ref "U7") (pin "24") (pinfunction "EECS_24") (pintype "output+no_connect"))
    )
    (net (code "61") (name "unconnected-(U7-EEDI-Pad26)") (class "Default")
      (node (ref "U7") (pin "26") (pinfunction "EEDI_26") (pintype "input+no_connect"))
    )
    (net (code "62") (name "unconnected-(U7-EEDO-Pad25)") (class "Default")
      (node (ref "U7") (pin "25") (pinfunction "EEDO_25") (pintype "output+no_connect"))
    )
    (net (code "63") (name "unconnected-(U7-GPIO3-Pad35)") (class "Default")
      (node (ref "U7") (pin "35") (pinfunction "GPIO3_35") (pintype "bidirectional+no_connect"))
    )
    (net (code "64") (name "unconnected-(U7-GPIO4-Pad36)") (class "Default")
      (node (ref "U7") (pin "36") (pinfunction "GPIO4_36") (pintype "bidirectional+no_connect"))
    )
    (net (code "65") (name "unconnected-(U7-GPIO5-Pad37)") (class "Default")
      (node (ref "U7") (pin "37") (pinfunction "GPIO5_37") (pintype "bidirectional+no_connect"))
    )
    (net (code "66") (name "unconnected-(U7-GPIO6-Pad42)") (class "Default")
      (node (ref "U7") (pin "42") (pinfunction "GPIO6_42") (pintype "bidirectional+no_connect"))
    )
    (net (code "67") (name "unconnected-(U7-GPIO7-Pad43)") (class "Default")
      (node (ref "U7") (pin "43") (pinfunction "GPIO7_43") (pintype "bidirectional+no_connect"))
    )
    (net (code "68") (name "unconnected-(U7-TDO-Pad31)") (class "Default")
      (node (ref "U7") (pin "31") (pinfunction "TDO_31") (pintype "output+no_connect"))
    )
    (net (code "69") (name "unconnected-(U7-TEST1-Pad13)") (class "Default")
      (node (ref "U7") (pin "13") (pinfunction "TEST1_13") (pintype "passive+no_connect"))
    )
    (net (code "70") (name "unconnected-(U7-TEST4-Pad47)") (class "Default")
      (node (ref "U7") (pin "47") (pinfunction "TEST4_47") (pintype "passive+no_connect"))
    )
  )
)
